# EddieBoardA.net
KiCad netlist of a schematic drawn in EAGLE
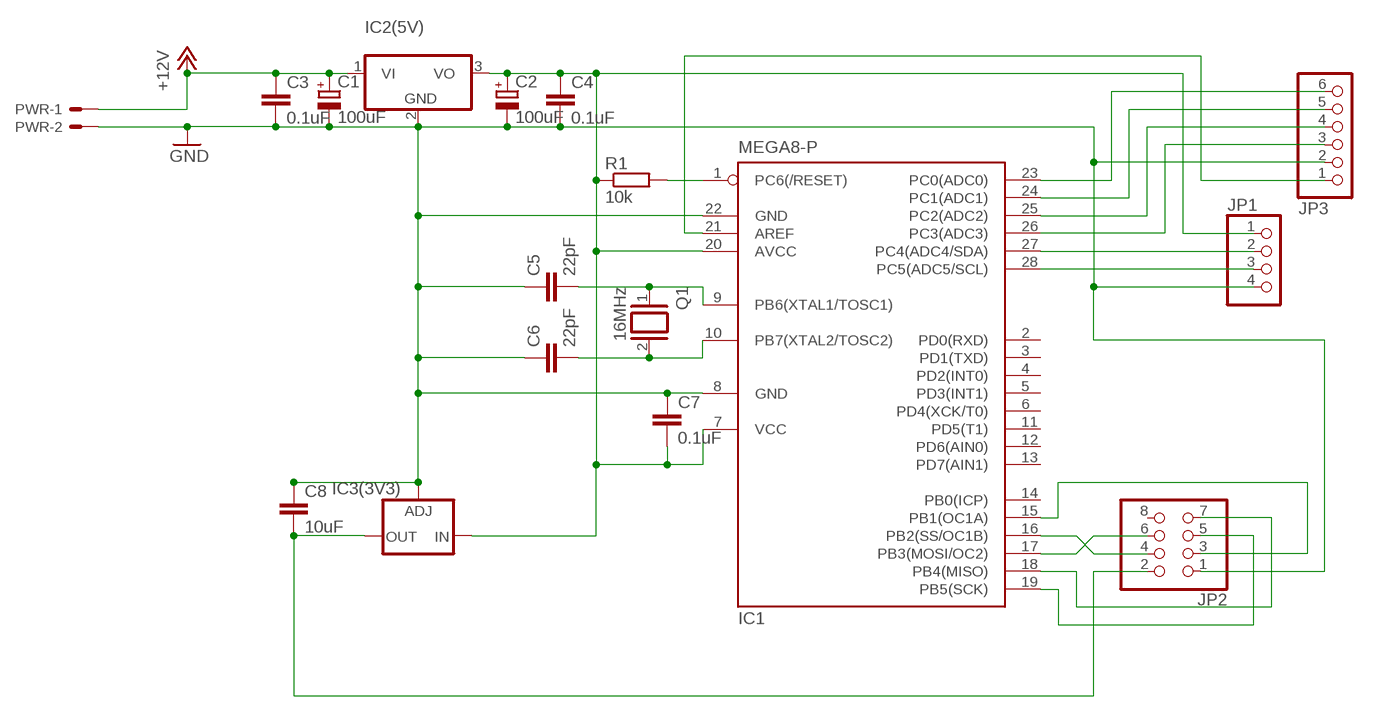
[diagram p0: schematic, sheet 1]

(export (version "E")
  (design (tool "Eeschema 10.0.6"))
  (components
    (comp (ref "C1")
      (value "100uF")
      (footprint "eagle-import:E2,5-6")
      (libsource (lib "eagle-import") (part "CPOL-EUE2.5-6"))
    )
    (comp (ref "C2")
      (value "100uF")
      (footprint "eagle-import:E2,5-6")
      (libsource (lib "eagle-import") (part "CPOL-EUE2.5-6"))
    )
    (comp (ref "C3")
      (value "0.1uF")
      (footprint "eagle-import:C025-025X050")
      (libsource (lib "eagle-import") (part "C-EU025-025X050"))
    )
    (comp (ref "C4")
      (value "0.1uF")
      (footprint "eagle-import:C025-025X050")
      (libsource (lib "eagle-import") (part "C-EU025-025X050"))
    )
    (comp (ref "C5")
      (value "22pF")
      (footprint "eagle-import:C025-025X050")
      (libsource (lib "eagle-import") (part "C-EU025-025X050"))
    )
    (comp (ref "C6")
      (value "22pF")
      (footprint "eagle-import:C025-025X050")
      (libsource (lib "eagle-import") (part "C-EU025-025X050"))
    )
    (comp (ref "C7")
      (value "0.1uF")
      (footprint "eagle-import:C025-025X050")
      (libsource (lib "eagle-import") (part "C-EU025-025X050"))
    )
    (comp (ref "C8")
      (value "10uF")
      (footprint "eagle-import:C025-025X050")
      (libsource (lib "eagle-import") (part "C-EU025-025X050"))
    )
    (comp (ref "IC1")
      (value "MEGA8-P")
      (footprint "eagle-import:DIL28-3")
      (libsource (lib "eagle-import") (part "MEGA8-P"))
    )
    (comp (ref "IC2(5V)")
      (value "7805TV")
      (footprint "eagle-import:TO220V")
      (libsource (lib "eagle-import") (part "78TV05"))
    )
    (comp (ref "IC3(3V3)")
      (value "LD117AV")
      (footprint "eagle-import:TO220L1")
      (libsource (lib "eagle-import") (part "LD117A?V"))
    )
    (comp (ref "JP1")
      (value "PINHD-1X4")
      (footprint "eagle-import:1X04")
      (libsource (lib "eagle-import") (part "PINHD-1X4"))
    )
    (comp (ref "JP2")
      (value "PINHD-2X4")
      (footprint "eagle-import:2X04")
      (libsource (lib "eagle-import") (part "PINHD-2X4"))
    )
    (comp (ref "JP3")
      (value "PINHD-1X6")
      (footprint "eagle-import:1X06")
      (libsource (lib "eagle-import") (part "PINHD-1X6"))
    )
    (comp (ref "PWR")
      (value "22-23-2021")
      (footprint "eagle-import:22-23-2021")
      (fields (field (name "MF") "MOLEX") (field (name "MPN") "PWR"))
      (libsource (lib "eagle-import") (part "22-23-2021"))
    )
    (comp (ref "Q1")
      (value "16MHz")
      (footprint "eagle-import:QS")
      (libsource (lib "eagle-import") (part "XTAL/S"))
    )
    (comp (ref "R1")
      (value "10k")
      (footprint "eagle-import:0207_12")
      (libsource (lib "eagle-import") (part "R-EU_0207/12"))
    )
  )
  (nets
    (net (code "1") (name "+12V") (class "Default")
      (node (ref "C1") (pin "+") (pinfunction "+_+") (pintype "passive"))
      (node (ref "C3") (pin "1") (pinfunction "1_1") (pintype "passive"))
      (node (ref "IC2(5V)") (pin "1") (pinfunction "VI_1") (pintype "input"))
      (node (ref "PWR") (pin "1") (pinfunction "S_1") (pintype "passive"))
    )
    (net (code "2") (name "GND") (class "Default")
      (node (ref "C1") (pin "-") (pinfunction "-_-") (pintype "passive"))
      (node (ref "C2") (pin "-") (pinfunction "-_-") (pintype "passive"))
      (node (ref "C3") (pin "2") (pinfunction "2_2") (pintype "passive"))
      (node (ref "C4") (pin "2") (pinfunction "2_2") (pintype "passive"))
      (node (ref "C5") (pin "1") (pinfunction "1_1") (pintype "passive"))
      (node (ref "C6") (pin "1") (pinfunction "1_1") (pintype "passive"))
      (node (ref "C7") (pin "1") (pinfunction "1_1") (pintype "passive"))
      (node (ref "C8") (pin "1") (pinfunction "1_1") (pintype "passive"))
      (node (ref "IC1") (pin "22") (pinfunction "GND_22") (pintype "power_in"))
      (node (ref "IC1") (pin "8") (pinfunction "GND_8") (pintype "power_in"))
      (node (ref "IC2(5V)") (pin "2") (pinfunction "GND_2") (pintype "passive"))
      (node (ref "IC3(3V3)") (pin "1") (pinfunction "ADJ_1") (pintype "input"))
      (node (ref "JP1") (pin "4") (pinfunction "4_4") (pintype "passive"))
      (node (ref "JP2") (pin "1") (pinfunction "1_1") (pintype "passive"))
      (node (ref "JP3") (pin "2") (pinfunction "2_2") (pintype "passive"))
      (node (ref "PWR") (pin "2") (pinfunction "S_2") (pintype "passive"))
    )
    (net (code "3") (name "Net-(IC1-AREF)") (class "Default")
      (node (ref "IC1") (pin "21") (pinfunction "AREF_21") (pintype "passive"))
      (node (ref "JP3") (pin "1") (pinfunction "1_1") (pintype "passive"))
    )
    (net (code "4") (name "Net-(IC1-AVCC)") (class "Default")
      (node (ref "C2") (pin "+") (pinfunction "+_+") (pintype "passive"))
      (node (ref "C4") (pin "1") (pinfunction "1_1") (pintype "passive"))
      (node (ref "C7") (pin "2") (pinfunction "2_2") (pintype "passive"))
      (node (ref "IC1") (pin "20") (pinfunction "AVCC_20") (pintype "power_in"))
      (node (ref "IC1") (pin "7") (pinfunction "VCC_7") (pintype "power_in"))
      (node (ref "IC2(5V)") (pin "3") (pinfunction "VO_3") (pintype "passive"))
      (node (ref "IC3(3V3)") (pin "3") (pinfunction "IN_3") (pintype "input"))
      (node (ref "JP1") (pin "1") (pinfunction "1_1") (pintype "passive"))
      (node (ref "R1") (pin "1") (pinfunction "1_1") (pintype "passive"))
    )
    (net (code "5") (name "Net-(IC1-PB1(OC1A))") (class "Default")
      (node (ref "IC1") (pin "15") (pinfunction "PB1(OC1A)_15") (pintype "bidirectional"))
      (node (ref "JP2") (pin "3") (pinfunction "3_3") (pintype "passive"))
    )
    (net (code "6") (name "Net-(IC1-PB2(SS{slash}OC1B))") (class "Default")
      (node (ref "IC1") (pin "16") (pinfunction "PB2(SS/OC1B)_16") (pintype "bidirectional"))
      (node (ref "JP2") (pin "4") (pinfunction "4_4") (pintype "passive"))
    )
    (net (code "7") (name "Net-(IC1-PB3(MOSI{slash}OC2))") (class "Default")
      (node (ref "IC1") (pin "17") (pinfunction "PB3(MOSI/OC2)_17") (pintype "bidirectional"))
      (node (ref "JP2") (pin "6") (pinfunction "6_6") (pintype "passive"))
    )
    (net (code "8") (name "Net-(IC1-PB4(MISO))") (class "Default")
      (node (ref "IC1") (pin "18") (pinfunction "PB4(MISO)_18") (pintype "bidirectional"))
      (node (ref "JP2") (pin "7") (pinfunction "7_7") (pintype "passive"))
    )
    (net (code "9") (name "Net-(IC1-PB5(SCK))") (class "Default")
      (node (ref "IC1") (pin "19") (pinfunction "PB5(SCK)_19") (pintype "bidirectional"))
      (node (ref "JP2") (pin "5") (pinfunction "5_5") (pintype "passive"))
    )
    (net (code "10") (name "Net-(IC1-PB6(XTAL1{slash}TOSC1))") (class "Default")
      (node (ref "C5") (pin "2") (pinfunction "2_2") (pintype "passive"))
      (node (ref "IC1") (pin "9") (pinfunction "PB6(XTAL1/TOSC1)_9") (pintype "bidirectional"))
      (node (ref "Q1") (pin "1") (pinfunction "1_1") (pintype "passive"))
    )
    (net (code "11") (name "Net-(IC1-PB7(XTAL2{slash}TOSC2))") (class "Default")
      (node (ref "C6") (pin "2") (pinfunction "2_2") (pintype "passive"))
      (node (ref "IC1") (pin "10") (pinfunction "PB7(XTAL2/TOSC2)_10") (pintype "bidirectional"))
      (node (ref "Q1") (pin "2") (pinfunction "2_2") (pintype "passive"))
    )
    (net (code "12") (name "Net-(IC1-PC0(ADC0))") (class "Default")
      (node (ref "IC1") (pin "23") (pinfunction "PC0(ADC0)_23") (pintype "bidirectional"))
      (node (ref "JP3") (pin "6") (pinfunction "6_6") (pintype "passive"))
    )
    (net (code "13") (name "Net-(IC1-PC1(ADC1))") (class "Default")
      (node (ref "IC1") (pin "24") (pinfunction "PC1(ADC1)_24") (pintype "bidirectional"))
      (node (ref "JP3") (pin "5") (pinfunction "5_5") (pintype "passive"))
    )
    (net (code "14") (name "Net-(IC1-PC2(ADC2))") (class "Default")
      (node (ref "IC1") (pin "25") (pinfunction "PC2(ADC2)_25") (pintype "bidirectional"))
      (node (ref "JP3") (pin "4") (pinfunction "4_4") (pintype "passive"))
    )
    (net (code "15") (name "Net-(IC1-PC3(ADC3))") (class "Default")
      (node (ref "IC1") (pin "26") (pinfunction "PC3(ADC3)_26") (pintype "bidirectional"))
      (node (ref "JP3") (pin "3") (pinfunction "3_3") (pintype "passive"))
    )
    (net (code "16") (name "Net-(IC1-PC4(ADC4{slash}SDA))") (class "Default")
      (node (ref "IC1") (pin "27") (pinfunction "PC4(ADC4/SDA)_27") (pintype "bidirectional"))
      (node (ref "JP1") (pin "2") (pinfunction "2_2") (pintype "passive"))
    )
    (net (code "17") (name "Net-(IC1-PC5(ADC5{slash}SCL))") (class "Default")
      (node (ref "IC1") (pin "28") (pinfunction "PC5(ADC5/SCL)_28") (pintype "bidirectional"))
      (node (ref "JP1") (pin "3") (pinfunction "3_3") (pintype "passive"))
    )
    (net (code "18") (name "Net-(IC1-PC6({slash}RESET))") (class "Default")
      (node (ref "IC1") (pin "1") (pinfunction "PC6(/RESET)_1") (pintype "bidirectional"))
      (node (ref "R1") (pin "2") (pinfunction "2_2") (pintype "passive"))
    )
    (net (code "19") (name "Net-(IC3(3V3)-OUT)") (class "Default")
      (node (ref "C8") (pin "2") (pinfunction "2_2") (pintype "passive"))
      (node (ref "IC3(3V3)") (pin "2") (pinfunction "OUT_2") (pintype "passive"))
      (node (ref "JP2") (pin "2") (pinfunction "2_2") (pintype "passive"))
    )
    (net (code "20") (name "unconnected-(IC1-PB0(ICP)-Pad14)") (class "Default")
      (node (ref "IC1") (pin "14") (pinfunction "PB0(ICP)_14") (pintype "bidirectional"))
    )
    (net (code "21") (name "unconnected-(IC1-PD0(RXD)-Pad2)") (class "Default")
      (node (ref "IC1") (pin "2") (pinfunction "PD0(RXD)_2") (pintype "bidirectional"))
    )
    (net (code "22") (name "unconnected-(IC1-PD1(TXD)-Pad3)") (class "Default")
      (node (ref "IC1") (pin "3") (pinfunction "PD1(TXD)_3") (pintype "bidirectional"))
    )
    (net (code "23") (name "unconnected-(IC1-PD2(INT0)-Pad4)") (class "Default")
      (node (ref "IC1") (pin "4") (pinfunction "PD2(INT0)_4") (pintype "bidirectional"))
    )
    (net (code "24") (name "unconnected-(IC1-PD3(INT1)-Pad5)") (class "Default")
      (node (ref "IC1") (pin "5") (pinfunction "PD3(INT1)_5") (pintype "bidirectional"))
    )
    (net (code "25") (name "unconnected-(IC1-PD4(XCK{slash}T0)-Pad6)") (class "Default")
      (node (ref "IC1") (pin "6") (pinfunction "PD4(XCK/T0)_6") (pintype "bidirectional"))
    )
    (net (code "26") (name "unconnected-(IC1-PD5(T1)-Pad11)") (class "Default")
      (node (ref "IC1") (pin "11") (pinfunction "PD5(T1)_11") (pintype "bidirectional"))
    )
    (net (code "27") (name "unconnected-(IC1-PD6(AIN0)-Pad12)") (class "Default")
      (node (ref "IC1") (pin "12") (pinfunction "PD6(AIN0)_12") (pintype "bidirectional"))
    )
    (net (code "28") (name "unconnected-(IC1-PD7(AIN1)-Pad13)") (class "Default")
      (node (ref "IC1") (pin "13") (pinfunction "PD7(AIN1)_13") (pintype "bidirectional"))
    )
    (net (code "29") (name "unconnected-(JP2-Pad8)") (class "Default")
      (node (ref "JP2") (pin "8") (pinfunction "8_8") (pintype "passive"))
    )
  )
)
